# bits2.net
KiCad netlist of a schematic drawn in EAGLE
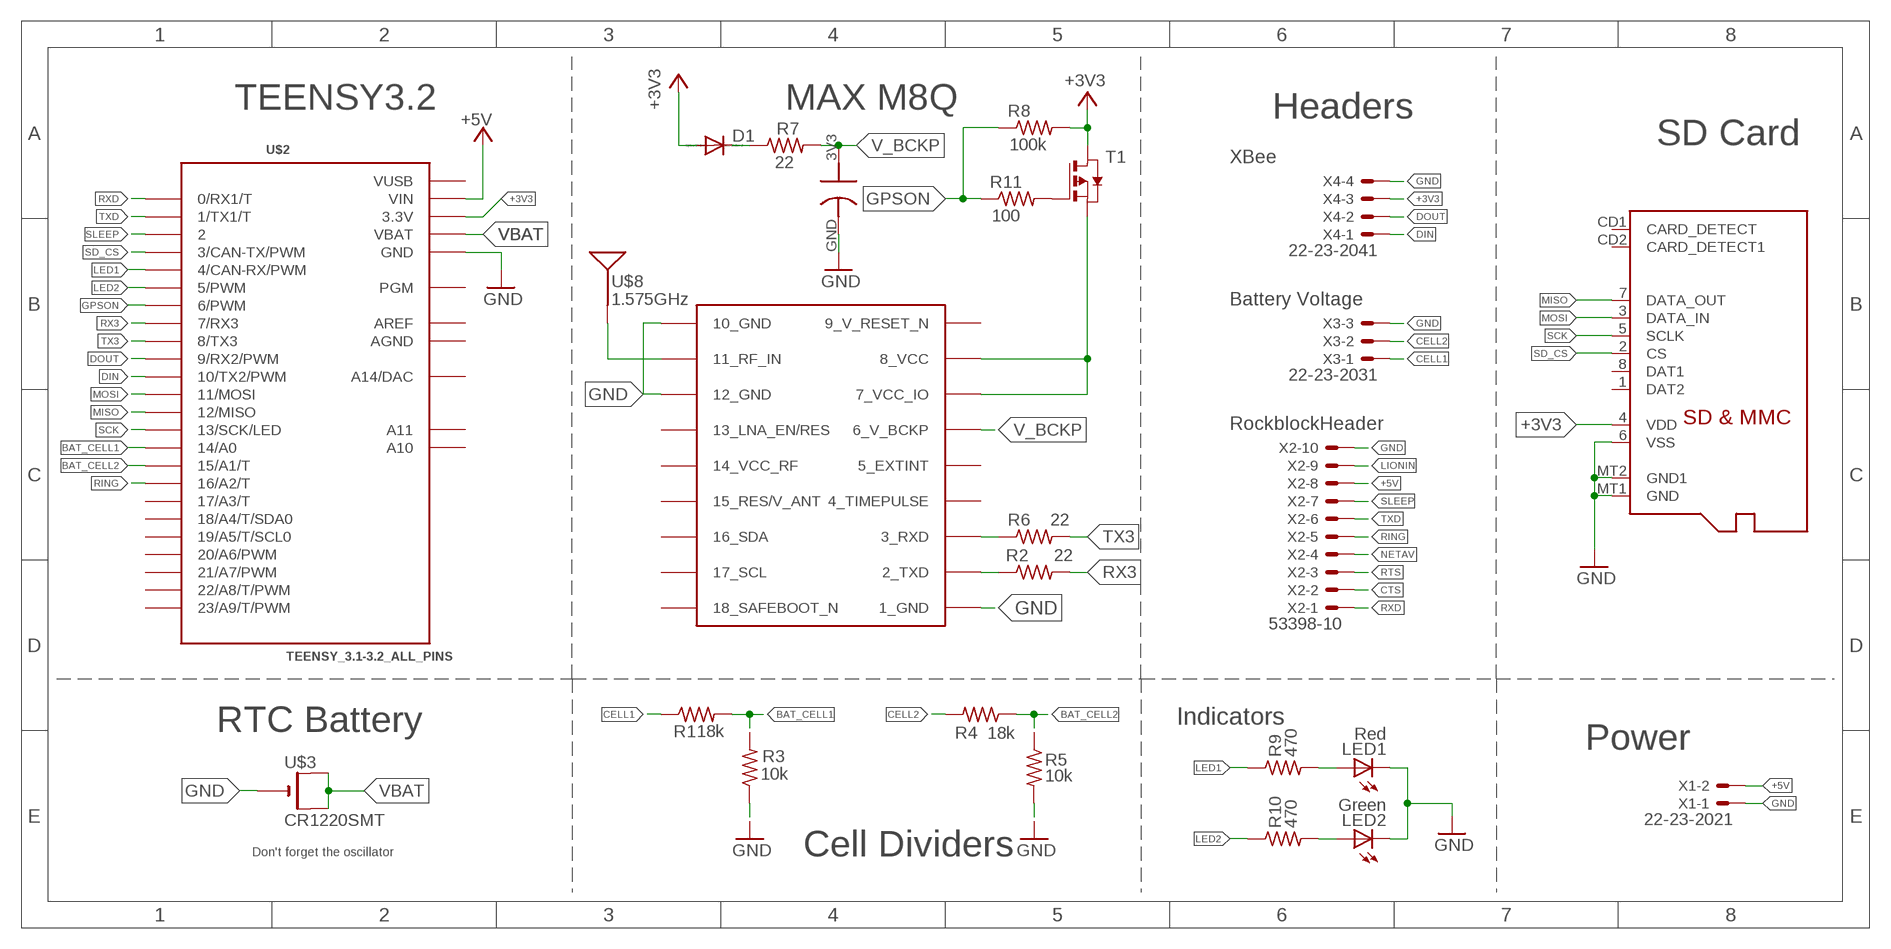
[diagram p0: schematic, sheet 1]

(export (version "E")
  (design (tool "Eeschema 10.0.6"))
  (components
    (comp (ref "C1")
      (value "DCK-3R3E204T614-E")
      (footprint "eagle-import:ELNASUPERCAP")
      (libsource (lib "eagle-import") (part "DCK-3R3E204T614-E"))
    )
    (comp (ref "D1")
      (value "DIODE-SOD523")
      (footprint "eagle-import:SOD523")
      (libsource (lib "eagle-import") (part "DIODE-SOD523"))
    )
    (comp (ref "LED1")
      (value "Red")
      (footprint "eagle-import:CHIP-LED0603")
      (libsource (lib "eagle-import") (part "LEDCHIP-LED0603"))
    )
    (comp (ref "LED2")
      (value "Green")
      (footprint "eagle-import:CHIP-LED0603")
      (libsource (lib "eagle-import") (part "LEDCHIP-LED0603"))
    )
    (comp (ref "R1")
      (value "18k")
      (footprint "eagle-import:R0603")
      (libsource (lib "eagle-import") (part "resistor_348_R-US_R0603"))
    )
    (comp (ref "R2")
      (value "22")
      (footprint "eagle-import:R0603")
      (libsource (lib "eagle-import") (part "R-US_R0603"))
    )
    (comp (ref "R3")
      (value "10k")
      (footprint "eagle-import:R0603")
      (libsource (lib "eagle-import") (part "resistor_348_R-US_R0603"))
    )
    (comp (ref "R4")
      (value "18k")
      (footprint "eagle-import:R0603")
      (libsource (lib "eagle-import") (part "resistor_348_R-US_R0603"))
    )
    (comp (ref "R5")
      (value "10k")
      (footprint "eagle-import:R0603")
      (libsource (lib "eagle-import") (part "resistor_348_R-US_R0603"))
    )
    (comp (ref "R6")
      (value "22")
      (footprint "eagle-import:R0603")
      (libsource (lib "eagle-import") (part "R-US_R0603"))
    )
    (comp (ref "R7")
      (value "22")
      (footprint "eagle-import:R0603")
      (libsource (lib "eagle-import") (part "R-US_R0603"))
    )
    (comp (ref "R8")
      (value "100k")
      (footprint "eagle-import:R0603")
      (libsource (lib "eagle-import") (part "R-US_R0603"))
    )
    (comp (ref "R9")
      (value "470")
      (footprint "eagle-import:R0603")
      (libsource (lib "eagle-import") (part "resistor_348_R-US_R0603"))
    )
    (comp (ref "R10")
      (value "470")
      (footprint "eagle-import:R0603")
      (libsource (lib "eagle-import") (part "resistor_348_R-US_R0603"))
    )
    (comp (ref "R11")
      (value "100")
      (footprint "eagle-import:R0603")
      (libsource (lib "eagle-import") (part "R-US_R0603"))
    )
    (comp (ref "T1")
      (value "PMOSSOT23")
      (footprint "eagle-import:SOT-23")
      (libsource (lib "eagle-import") (part "PMOSSOT23"))
    )
    (comp (ref "U$1")
      (value "MICROSD")
      (footprint "eagle-import:MICROSD")
      (libsource (lib "eagle-import") (part "MICROSD"))
    )
    (comp (ref "U$2")
      (value "TEENSY_3.1-3.2_ALL_PINS")
      (footprint "eagle-import:TEENSY_3.0-3.2&LC_ALL_PINS")
      (libsource (lib "eagle-import") (part "TEENSY_3.1-3.2_ALL_PINS"))
    )
    (comp (ref "U$3")
      (value "CR1220SMT")
      (footprint "eagle-import:CR1220-SMD")
      (libsource (lib "eagle-import") (part "CR1220SMT"))
    )
    (comp (ref "U$7")
      (value "MAX-M8")
      (footprint "eagle-import:MAX-M8")
      (libsource (lib "eagle-import") (part "MAX-M8"))
    )
    (comp (ref "U$8")
      (value "1.575GHz")
      (footprint "eagle-import:SPARKFUN-GPS_ANT-GPS-2X7MM")
      (libsource (lib "eagle-import") (part "SPARKFUN-GPS_ANTENNAGPS-2X7MM"))
    )
    (comp (ref "X1")
      (value "22-23-2021")
      (footprint "eagle-import:22-23-2021")
      (fields (field (name "MF") "MOLEX"))
      (libsource (lib "eagle-import") (part "22-23-2021"))
    )
    (comp (ref "X2")
      (value "53398-10")
      (footprint "eagle-import:53398-10")
      (fields (field (name "MF") "MOLEX") (field (name "MPN") "53398-1071"))
      (libsource (lib "eagle-import") (part "53?-10398"))
    )
    (comp (ref "X3")
      (value "22-23-2031")
      (footprint "eagle-import:22-23-2031")
      (fields (field (name "MF") "MOLEX"))
      (libsource (lib "eagle-import") (part "22-23-2031"))
    )
    (comp (ref "X4")
      (value "22-23-2041")
      (footprint "eagle-import:22-23-2041")
      (fields (field (name "MF") "MOLEX"))
      (libsource (lib "eagle-import") (part "22-23-2041"))
    )
  )
  (nets
    (net (code "1") (name "+3V3") (class "Default")
      (node (ref "D1") (pin "A") (pinfunction "A_A") (pintype "passive"))
      (node (ref "R8") (pin "2") (pinfunction "2_2") (pintype "passive"))
      (node (ref "T1") (pin "1") (pinfunction "D_1") (pintype "passive"))
      (node (ref "U$1") (pin "4") (pinfunction "VDD_4") (pintype "power_in"))
      (node (ref "U$2") (pin "3.3V") (pinfunction "3.3V_3.3V") (pintype "power_in"))
      (node (ref "U$2") (pin "3.3V1") (pinfunction "3.3V_3.3V1") (pintype "power_in"))
      (node (ref "X4") (pin "3") (pinfunction "S_3") (pintype "passive"))
    )
    (net (code "2") (name "+5V") (class "Default")
      (node (ref "U$2") (pin "VIN") (pinfunction "VIN_VIN") (pintype "power_in"))
      (node (ref "X1") (pin "2") (pinfunction "S_2") (pintype "passive"))
      (node (ref "X2") (pin "8") (pinfunction "S_8") (pintype "passive"))
    )
    (net (code "3") (name "/9_V_RESET_N") (class "Default")
      (node (ref "U$7") (pin "9_RESET_N") (pinfunction "9_V_RESET_N_9_RESET_N") (pintype "power_in"))
    )
    (net (code "4") (name "/AGND") (class "Default")
      (node (ref "U$2") (pin "AGND") (pinfunction "AGND_AGND") (pintype "power_in"))
    )
    (net (code "5") (name "/AREF") (class "Default")
      (node (ref "U$2") (pin "AREF") (pinfunction "AREF_AREF") (pintype "power_in"))
    )
    (net (code "6") (name "/VUSB") (class "Default")
      (node (ref "U$2") (pin "VUSB") (pinfunction "VUSB_VUSB") (pintype "power_in"))
    )
    (net (code "7") (name "BAT_CELL1") (class "Default")
      (node (ref "R1") (pin "2") (pinfunction "2_2") (pintype "passive"))
      (node (ref "R3") (pin "2") (pinfunction "2_2") (pintype "passive"))
      (node (ref "U$2") (pin "14/A0") (pinfunction "14/A0_14/A0") (pintype "bidirectional"))
    )
    (net (code "8") (name "BAT_CELL2") (class "Default")
      (node (ref "R4") (pin "1") (pinfunction "1_1") (pintype "passive"))
      (node (ref "R5") (pin "1") (pinfunction "1_1") (pintype "passive"))
      (node (ref "U$2") (pin "15/A1") (pinfunction "15/A1/T_15/A1") (pintype "bidirectional"))
    )
    (net (code "9") (name "CELL1") (class "Default")
      (node (ref "R1") (pin "1") (pinfunction "1_1") (pintype "passive"))
      (node (ref "X3") (pin "1") (pinfunction "S_1") (pintype "passive"))
    )
    (net (code "10") (name "CELL2") (class "Default")
      (node (ref "R4") (pin "2") (pinfunction "2_2") (pintype "passive"))
      (node (ref "X3") (pin "2") (pinfunction "S_2") (pintype "passive"))
    )
    (net (code "11") (name "CTS") (class "Default")
      (node (ref "X2") (pin "2") (pinfunction "S_2") (pintype "passive"))
    )
    (net (code "12") (name "DIN") (class "Default")
      (node (ref "U$2") (pin "10") (pinfunction "10/TX2/PWM_10") (pintype "bidirectional"))
      (node (ref "X4") (pin "1") (pinfunction "S_1") (pintype "passive"))
    )
    (net (code "13") (name "DOUT") (class "Default")
      (node (ref "U$2") (pin "9") (pinfunction "9/RX2/PWM_9") (pintype "bidirectional"))
      (node (ref "X4") (pin "2") (pinfunction "S_2") (pintype "passive"))
    )
    (net (code "14") (name "GND") (class "Default")
      (node (ref "C1") (pin "GND") (pinfunction "GND_GND") (pintype "bidirectional"))
      (node (ref "LED1") (pin "C") (pinfunction "C_C") (pintype "passive"))
      (node (ref "LED2") (pin "C") (pinfunction "C_C") (pintype "passive"))
      (node (ref "R3") (pin "1") (pinfunction "1_1") (pintype "passive"))
      (node (ref "R5") (pin "2") (pinfunction "2_2") (pintype "passive"))
      (node (ref "U$1") (pin "6") (pinfunction "VSS_6") (pintype "power_in"))
      (node (ref "U$1") (pin "MT1") (pinfunction "GND_MT1") (pintype "power_in"))
      (node (ref "U$1") (pin "MT2") (pinfunction "GND1_MT2") (pintype "power_in"))
      (node (ref "U$2") (pin "GND") (pinfunction "GND_GND") (pintype "power_in"))
      (node (ref "U$2") (pin "GND1") (pinfunction "GND_GND1") (pintype "power_in"))
      (node (ref "U$3") (pin "-") (pinfunction "-_-") (pintype "passive"))
      (node (ref "U$7") (pin "10_GND") (pinfunction "10_GND_10_GND") (pintype "power_in"))
      (node (ref "U$7") (pin "12_GND") (pinfunction "12_GND_12_GND") (pintype "power_in"))
      (node (ref "U$7") (pin "1_GND") (pinfunction "1_GND_1_GND") (pintype "power_in"))
      (node (ref "X1") (pin "1") (pinfunction "S_1") (pintype "passive"))
      (node (ref "X2") (pin "10") (pinfunction "S_10") (pintype "passive"))
      (node (ref "X3") (pin "3") (pinfunction "S_3") (pintype "passive"))
      (node (ref "X4") (pin "4") (pinfunction "S_4") (pintype "passive"))
    )
    (net (code "15") (name "GPSON") (class "Default")
      (node (ref "R11") (pin "1") (pinfunction "1_1") (pintype "passive"))
      (node (ref "R8") (pin "1") (pinfunction "1_1") (pintype "passive"))
      (node (ref "U$2") (pin "6") (pinfunction "6/PWM_6") (pintype "bidirectional"))
    )
    (net (code "16") (name "LED1") (class "Default")
      (node (ref "R9") (pin "1") (pinfunction "1_1") (pintype "passive"))
      (node (ref "U$2") (pin "4") (pinfunction "4/CAN-RX/PWM_4") (pintype "bidirectional"))
    )
    (net (code "17") (name "LED2") (class "Default")
      (node (ref "R10") (pin "1") (pinfunction "1_1") (pintype "passive"))
      (node (ref "U$2") (pin "5") (pinfunction "5/PWM_5") (pintype "bidirectional"))
    )
    (net (code "18") (name "LIONIN") (class "Default")
      (node (ref "X2") (pin "9") (pinfunction "S_9") (pintype "passive"))
    )
    (net (code "19") (name "MISO") (class "Default")
      (node (ref "U$1") (pin "7") (pinfunction "DATA_OUT_7") (pintype "output"))
      (node (ref "U$2") (pin "12") (pinfunction "12/MISO_12") (pintype "bidirectional"))
    )
    (net (code "20") (name "MOSI") (class "Default")
      (node (ref "U$1") (pin "3") (pinfunction "DATA_IN_3") (pintype "input"))
      (node (ref "U$2") (pin "11") (pinfunction "11/MOSI_11") (pintype "bidirectional"))
    )
    (net (code "21") (name "NETAV") (class "Default")
      (node (ref "X2") (pin "4") (pinfunction "S_4") (pintype "passive"))
    )
    (net (code "22") (name "Net-(D1-PadC)") (class "Default")
      (node (ref "D1") (pin "C") (pinfunction "C_C") (pintype "passive"))
      (node (ref "R7") (pin "1") (pinfunction "1_1") (pintype "passive"))
    )
    (net (code "23") (name "Net-(LED1-PadA)") (class "Default")
      (node (ref "LED1") (pin "A") (pinfunction "A_A") (pintype "passive"))
      (node (ref "R9") (pin "2") (pinfunction "2_2") (pintype "passive"))
    )
    (net (code "24") (name "Net-(LED2-PadA)") (class "Default")
      (node (ref "LED2") (pin "A") (pinfunction "A_A") (pintype "passive"))
      (node (ref "R10") (pin "2") (pinfunction "2_2") (pintype "passive"))
    )
    (net (code "25") (name "Net-(R2-Pad1)") (class "Default")
      (node (ref "R2") (pin "1") (pinfunction "1_1") (pintype "passive"))
      (node (ref "U$7") (pin "2_TXD") (pinfunction "2_TXD_2_TXD") (pintype "bidirectional"))
    )
    (net (code "26") (name "Net-(R6-Pad1)") (class "Default")
      (node (ref "R6") (pin "1") (pinfunction "1_1") (pintype "passive"))
      (node (ref "U$7") (pin "3_RXD") (pinfunction "3_RXD_3_RXD") (pintype "bidirectional"))
    )
    (net (code "27") (name "Net-(T1-G)") (class "Default")
      (node (ref "R11") (pin "2") (pinfunction "2_2") (pintype "passive"))
      (node (ref "T1") (pin "3") (pinfunction "G_3") (pintype "passive"))
    )
    (net (code "28") (name "Net-(T1-S)") (class "Default")
      (node (ref "T1") (pin "2") (pinfunction "S_2") (pintype "passive"))
      (node (ref "U$7") (pin "7_VCC_IO") (pinfunction "7_VCC_IO_7_VCC_IO") (pintype "power_in"))
      (node (ref "U$7") (pin "8_VCC") (pinfunction "8_VCC_8_VCC") (pintype "power_in"))
    )
    (net (code "29") (name "Net-(U$8-SIGNAL)") (class "Default")
      (node (ref "U$7") (pin "11_RF_IN") (pinfunction "11_RF_IN_11_RF_IN") (pintype "bidirectional"))
      (node (ref "U$8") (pin "1") (pinfunction "SIGNAL_1") (pintype "bidirectional"))
    )
    (net (code "30") (name "RING") (class "Default")
      (node (ref "U$2") (pin "16/A2") (pinfunction "16/A2/T_16/A2") (pintype "bidirectional"))
      (node (ref "X2") (pin "5") (pinfunction "S_5") (pintype "passive"))
    )
    (net (code "31") (name "RTS") (class "Default")
      (node (ref "X2") (pin "3") (pinfunction "S_3") (pintype "passive"))
    )
    (net (code "32") (name "RX3") (class "Default")
      (node (ref "R2") (pin "2") (pinfunction "2_2") (pintype "passive"))
      (node (ref "U$2") (pin "7") (pinfunction "7/RX3_7") (pintype "bidirectional"))
    )
    (net (code "33") (name "RXD") (class "Default")
      (node (ref "U$2") (pin "0") (pinfunction "0/RX1/T_0") (pintype "bidirectional"))
      (node (ref "X2") (pin "1") (pinfunction "S_1") (pintype "passive"))
    )
    (net (code "34") (name "SCK") (class "Default")
      (node (ref "U$1") (pin "5") (pinfunction "SCLK_5") (pintype "input"))
      (node (ref "U$2") (pin "13") (pinfunction "13/SCK/LED_13") (pintype "bidirectional"))
    )
    (net (code "35") (name "SD_CS") (class "Default")
      (node (ref "U$1") (pin "2") (pinfunction "CS_2") (pintype "input"))
      (node (ref "U$2") (pin "3") (pinfunction "3/CAN-TX/PWM_3") (pintype "bidirectional"))
    )
    (net (code "36") (name "SLEEP") (class "Default")
      (node (ref "U$2") (pin "2") (pinfunction "2_2") (pintype "bidirectional"))
      (node (ref "X2") (pin "7") (pinfunction "S_7") (pintype "passive"))
    )
    (net (code "37") (name "TX3") (class "Default")
      (node (ref "R6") (pin "2") (pinfunction "2_2") (pintype "passive"))
      (node (ref "U$2") (pin "8") (pinfunction "8/TX3_8") (pintype "bidirectional"))
    )
    (net (code "38") (name "TXD") (class "Default")
      (node (ref "U$2") (pin "1") (pinfunction "1/TX1/T_1") (pintype "bidirectional"))
      (node (ref "X2") (pin "6") (pinfunction "S_6") (pintype "passive"))
    )
    (net (code "39") (name "VBAT") (class "Default")
      (node (ref "U$2") (pin "VBAT") (pinfunction "VBAT_VBAT") (pintype "power_in"))
      (node (ref "U$3") (pin "+$1") (pinfunction "+_+$1") (pintype "passive"))
      (node (ref "U$3") (pin "+$2") (pinfunction "+1_+$2") (pintype "passive"))
    )
    (net (code "40") (name "V_BCKP") (class "Default")
      (node (ref "C1") (pin "3V3") (pinfunction "3V3_3V3") (pintype "bidirectional"))
      (node (ref "R7") (pin "2") (pinfunction "2_2") (pintype "passive"))
      (node (ref "U$7") (pin "6_V_BCKP") (pinfunction "6_V_BCKP_6_V_BCKP") (pintype "bidirectional"))
    )
    (net (code "41") (name "unconnected-(U$1-CARD_DETECT-PadCD1)") (class "Default")
      (node (ref "U$1") (pin "CD1") (pinfunction "CARD_DETECT_CD1") (pintype "passive"))
    )
    (net (code "42") (name "unconnected-(U$1-CARD_DETECT1-PadCD2)") (class "Default")
      (node (ref "U$1") (pin "CD2") (pinfunction "CARD_DETECT1_CD2") (pintype "passive"))
    )
    (net (code "43") (name "unconnected-(U$1-DAT1-Pad8)") (class "Default")
      (node (ref "U$1") (pin "8") (pinfunction "DAT1_8") (pintype "bidirectional"))
    )
    (net (code "44") (name "unconnected-(U$1-DAT2-Pad1)") (class "Default")
      (node (ref "U$1") (pin "1") (pinfunction "DAT2_1") (pintype "bidirectional"))
    )
    (net (code "45") (name "unconnected-(U$2-17{slash}A3{slash}T-Pad17{slash}A3)") (class "Default")
      (node (ref "U$2") (pin "17/A3") (pinfunction "17/A3/T_17/A3") (pintype "bidirectional"))
    )
    (net (code "46") (name "unconnected-(U$2-18{slash}A4{slash}T{slash}SDA0-Pad18{slash}A4)") (class "Default")
      (node (ref "U$2") (pin "18/A4") (pinfunction "18/A4/T/SDA0_18/A4") (pintype "bidirectional"))
    )
    (net (code "47") (name "unconnected-(U$2-19{slash}A5{slash}T{slash}SCL0-Pad19{slash}A5)") (class "Default")
      (node (ref "U$2") (pin "19/A5") (pinfunction "19/A5/T/SCL0_19/A5") (pintype "bidirectional"))
    )
    (net (code "48") (name "unconnected-(U$2-20{slash}A6{slash}PWM-Pad20{slash}A6)") (class "Default")
      (node (ref "U$2") (pin "20/A6") (pinfunction "20/A6/PWM_20/A6") (pintype "bidirectional"))
    )
    (net (code "49") (name "unconnected-(U$2-21{slash}A7{slash}PWM-Pad21{slash}A7)") (class "Default")
      (node (ref "U$2") (pin "21/A7") (pinfunction "21/A7/PWM_21/A7") (pintype "bidirectional"))
    )
    (net (code "50") (name "unconnected-(U$2-22{slash}A8{slash}T{slash}PWM-Pad22{slash}A8)") (class "Default")
      (node (ref "U$2") (pin "22/A8") (pinfunction "22/A8/T/PWM_22/A8") (pintype "bidirectional"))
    )
    (net (code "51") (name "unconnected-(U$2-23{slash}A9{slash}T{slash}PWM-Pad23{slash}A9)") (class "Default")
      (node (ref "U$2") (pin "23/A9") (pinfunction "23/A9/T/PWM_23/A9") (pintype "bidirectional"))
    )
    (net (code "52") (name "unconnected-(U$2-A14{slash}DAC-PadRESET{slash}DAC)") (class "Default")
      (node (ref "U$2") (pin "RESET/DAC") (pinfunction "A14/DAC_RESET/DAC") (pintype "bidirectional"))
    )
    (net (code "53") (name "unconnected-(U$2-PadA10)") (class "Default")
      (node (ref "U$2") (pin "A10") (pinfunction "A10_A10") (pintype "bidirectional"))
    )
    (net (code "54") (name "unconnected-(U$2-PadA11)") (class "Default")
      (node (ref "U$2") (pin "A11") (pinfunction "A11_A11") (pintype "bidirectional"))
    )
    (net (code "55") (name "unconnected-(U$2-PadPGM)") (class "Default")
      (node (ref "U$2") (pin "PGM") (pinfunction "PGM_PGM") (pintype "bidirectional"))
    )
    (net (code "56") (name "unconnected-(U$7-13_LNA_EN{slash}RES-Pad13_LNA_EN)") (class "Default")
      (node (ref "U$7") (pin "13_LNA_EN") (pinfunction "13_LNA_EN/RES_13_LNA_EN") (pintype "bidirectional"))
    )
    (net (code "57") (name "unconnected-(U$7-15_RES{slash}V_ANT-Pad15_V_ANT{slash}RESERVED)") (class "Default")
      (node (ref "U$7") (pin "15_V_ANT/RESERVED") (pinfunction "15_RES/V_ANT_15_V_ANT/RESERVED") (pintype "bidirectional"))
    )
    (net (code "58") (name "unconnected-(U$7-Pad4_TIMEPULSE)") (class "Default")
      (node (ref "U$7") (pin "4_TIMEPULSE") (pinfunction "4_TIMEPULSE_4_TIMEPULSE") (pintype "bidirectional"))
    )
    (net (code "59") (name "unconnected-(U$7-Pad5_EXTINT)") (class "Default")
      (node (ref "U$7") (pin "5_EXTINT") (pinfunction "5_EXTINT_5_EXTINT") (pintype "bidirectional"))
    )
    (net (code "60") (name "unconnected-(U$7-Pad14_VCC_RF)") (class "Default")
      (node (ref "U$7") (pin "14_VCC_RF") (pinfunction "14_VCC_RF_14_VCC_RF") (pintype "bidirectional"))
    )
    (net (code "61") (name "unconnected-(U$7-Pad16_SDA)") (class "Default")
      (node (ref "U$7") (pin "16_SDA") (pinfunction "16_SDA_16_SDA") (pintype "bidirectional"))
    )
    (net (code "62") (name "unconnected-(U$7-Pad17_SCL)") (class "Default")
      (node (ref "U$7") (pin "17_SCL") (pinfunction "17_SCL_17_SCL") (pintype "bidirectional"))
    )
    (net (code "63") (name "unconnected-(U$7-Pad18_SAFEBOOT_N)") (class "Default")
      (node (ref "U$7") (pin "18_SAFEBOOT_N") (pinfunction "18_SAFEBOOT_N_18_SAFEBOOT_N") (pintype "bidirectional"))
    )
  )
)
